# pll-filters.net
KiCad netlist of a schematic drawn in Altium Designer
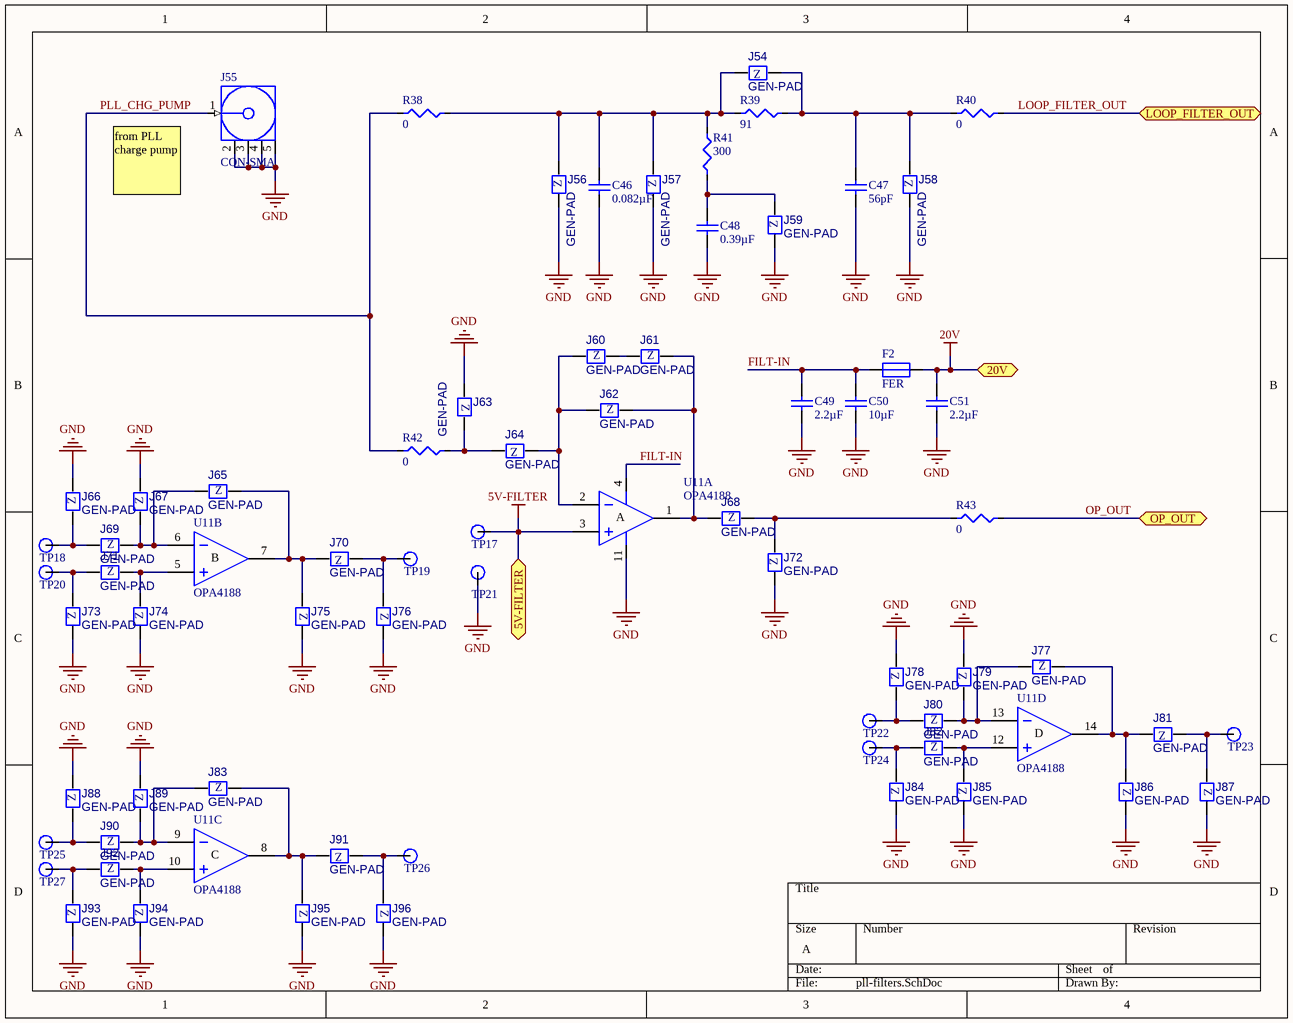
[diagram p0: pll-filters.SchDoc]

(export (version "E")
  (design (tool "Eeschema 10.0.6"))
  (components
    (comp (ref "C46")
      (value "0.082µF")
      (footprint "C0603-0.8MM")
      (description "Capacitor")
      (fields (field (name "EE PART NUMBER") "EE-CAP-00005") (field (name "VOLTAGE") "25V"))
      (libsource (lib "EE") (part "CAP"))
    )
    (comp (ref "C47")
      (value "56pF")
      (footprint "0402-0.55mm")
      (description "Capacitor")
      (fields (field (name "EE PART NUMBER") "EE-CAP-00007") (field (name "VOLTAGE") "50V"))
      (libsource (lib "EE") (part "CAP"))
    )
    (comp (ref "C48")
      (value "0.39µF")
      (footprint "0805-1.35MM")
      (description "Capacitor")
      (fields (field (name "EE PART NUMBER") "EE-CAP-00006") (field (name "VOLTAGE") "25V"))
      (libsource (lib "EE") (part "CAP"))
    )
    (comp (ref "C49")
      (value "2.2µF")
      (footprint "0402-0.55mm")
      (description "Capacitor")
      (fields (field (name "EE PART NUMBER") "EE-CAP-00003") (field (name "VOLTAGE") "35V"))
      (libsource (lib "EE") (part "CAP"))
    )
    (comp (ref "C50")
      (value "10µF")
      (footprint "C0805-1.25MM")
      (description "Capacitor")
      (fields (field (name "EE PART NUMBER") "EE-CAP-00002") (field (name "VOLTAGE") "35V"))
      (libsource (lib "EE") (part "CAP"))
    )
    (comp (ref "C51")
      (value "2.2µF")
      (footprint "0402-0.55mm")
      (description "Capacitor")
      (fields (field (name "EE PART NUMBER") "EE-CAP-00003") (field (name "VOLTAGE") "35V"))
      (libsource (lib "EE") (part "CAP"))
    )
    (comp (ref "F2")
      (value "FER")
      (footprint "0603-0.8mm")
      (fields
        (field (name "EE PART NUMBER") "EE-FER-00001")
        (field (name "MANUFACTURER") "Laird-Signal")
        (field (name "MANUFACTURER PART NUMBER") "HZ0603A222R-10")
      )
      (libsource (lib "EE") (part "FER"))
    )
    (comp (ref "J54")
      (value "GEN-PAD")
      (footprint "0402-DNP")
      (description "Generic Component")
      (fields (field (name "EE PART NUMBER") "EE-GEN-00002"))
      (libsource (lib "EE") (part "GEN-PAD"))
    )
    (comp (ref "J55")
      (value "CON-SMA")
      (footprint "CON-COAX")
      (fields
        (field (name "EE PART NUMBER") "EE-CON-00001")
        (field (name "MANUFACTURER") "East Coast Microwave")
        (field (name "MANUFACTURER PART NUMBER") "PSF-S01-008")
      )
      (libsource (lib "EE") (part "CON-SMA"))
    )
    (comp (ref "J56")
      (value "GEN-PAD")
      (footprint "0805-DNP")
      (description "Generic Component")
      (fields (field (name "EE PART NUMBER") "EE-GEN-00001"))
      (libsource (lib "EE") (part "GEN-PAD"))
    )
    (comp (ref "J57")
      (value "GEN-PAD")
      (footprint "0402-DNP")
      (description "Generic Component")
      (fields (field (name "EE PART NUMBER") "EE-GEN-00002"))
      (libsource (lib "EE") (part "GEN-PAD"))
    )
    (comp (ref "J58")
      (value "GEN-PAD")
      (footprint "0805-DNP")
      (description "Generic Component")
      (fields (field (name "EE PART NUMBER") "EE-GEN-00001"))
      (libsource (lib "EE") (part "GEN-PAD"))
    )
    (comp (ref "J59")
      (value "GEN-PAD")
      (footprint "0402-DNP")
      (description "Generic Component")
      (fields (field (name "EE PART NUMBER") "EE-GEN-00002"))
      (libsource (lib "EE") (part "GEN-PAD"))
    )
    (comp (ref "J60")
      (value "GEN-PAD")
      (footprint "0805-DNP")
      (description "Generic Component")
      (fields (field (name "EE PART NUMBER") "EE-GEN-00001"))
      (libsource (lib "EE") (part "GEN-PAD"))
    )
    (comp (ref "J61")
      (value "GEN-PAD")
      (footprint "0805-DNP")
      (description "Generic Component")
      (fields (field (name "EE PART NUMBER") "EE-GEN-00001"))
      (libsource (lib "EE") (part "GEN-PAD"))
    )
    (comp (ref "J62")
      (value "GEN-PAD")
      (footprint "0805-DNP")
      (description "Generic Component")
      (fields (field (name "EE PART NUMBER") "EE-GEN-00001"))
      (libsource (lib "EE") (part "GEN-PAD"))
    )
    (comp (ref "J63")
      (value "GEN-PAD")
      (footprint "0805-DNP")
      (description "Generic Component")
      (fields (field (name "EE PART NUMBER") "EE-GEN-00001"))
      (libsource (lib "EE") (part "GEN-PAD"))
    )
    (comp (ref "J64")
      (value "GEN-PAD")
      (footprint "0805-DNP")
      (description "Generic Component")
      (fields (field (name "EE PART NUMBER") "EE-GEN-00001"))
      (libsource (lib "EE") (part "GEN-PAD"))
    )
    (comp (ref "J65")
      (value "GEN-PAD")
      (footprint "0805-DNP")
      (description "Generic Component")
      (fields (field (name "EE PART NUMBER") "EE-GEN-00001"))
      (libsource (lib "EE") (part "GEN-PAD"))
    )
    (comp (ref "J66")
      (value "GEN-PAD")
      (footprint "0805-DNP")
      (description "Generic Component")
      (fields (field (name "EE PART NUMBER") "EE-GEN-00001"))
      (libsource (lib "EE") (part "GEN-PAD"))
    )
    (comp (ref "J67")
      (value "GEN-PAD")
      (footprint "0805-DNP")
      (description "Generic Component")
      (fields (field (name "EE PART NUMBER") "EE-GEN-00001"))
      (libsource (lib "EE") (part "GEN-PAD"))
    )
    (comp (ref "J68")
      (value "GEN-PAD")
      (footprint "0805-DNP")
      (description "Generic Component")
      (fields (field (name "EE PART NUMBER") "EE-GEN-00001"))
      (libsource (lib "EE") (part "GEN-PAD"))
    )
    (comp (ref "J69")
      (value "GEN-PAD")
      (footprint "0805-DNP")
      (description "Generic Component")
      (fields (field (name "EE PART NUMBER") "EE-GEN-00001"))
      (libsource (lib "EE") (part "GEN-PAD"))
    )
    (comp (ref "J70")
      (value "GEN-PAD")
      (footprint "0805-DNP")
      (description "Generic Component")
      (fields (field (name "EE PART NUMBER") "EE-GEN-00001"))
      (libsource (lib "EE") (part "GEN-PAD"))
    )
    (comp (ref "J71")
      (value "GEN-PAD")
      (footprint "0805-DNP")
      (description "Generic Component")
      (fields (field (name "EE PART NUMBER") "EE-GEN-00001"))
      (libsource (lib "EE") (part "GEN-PAD"))
    )
    (comp (ref "J72")
      (value "GEN-PAD")
      (footprint "0805-DNP")
      (description "Generic Component")
      (fields (field (name "EE PART NUMBER") "EE-GEN-00001"))
      (libsource (lib "EE") (part "GEN-PAD"))
    )
    (comp (ref "J73")
      (value "GEN-PAD")
      (footprint "0805-DNP")
      (description "Generic Component")
      (fields (field (name "EE PART NUMBER") "EE-GEN-00001"))
      (libsource (lib "EE") (part "GEN-PAD"))
    )
    (comp (ref "J74")
      (value "GEN-PAD")
      (footprint "0805-DNP")
      (description "Generic Component")
      (fields (field (name "EE PART NUMBER") "EE-GEN-00001"))
      (libsource (lib "EE") (part "GEN-PAD"))
    )
    (comp (ref "J75")
      (value "GEN-PAD")
      (footprint "0805-DNP")
      (description "Generic Component")
      (fields (field (name "EE PART NUMBER") "EE-GEN-00001"))
      (libsource (lib "EE") (part "GEN-PAD"))
    )
    (comp (ref "J76")
      (value "GEN-PAD")
      (footprint "0805-DNP")
      (description "Generic Component")
      (fields (field (name "EE PART NUMBER") "EE-GEN-00001"))
      (libsource (lib "EE") (part "GEN-PAD"))
    )
    (comp (ref "J77")
      (value "GEN-PAD")
      (footprint "0805-DNP")
      (description "Generic Component")
      (fields (field (name "EE PART NUMBER") "EE-GEN-00001"))
      (libsource (lib "EE") (part "GEN-PAD"))
    )
    (comp (ref "J78")
      (value "GEN-PAD")
      (footprint "0805-DNP")
      (description "Generic Component")
      (fields (field (name "EE PART NUMBER") "EE-GEN-00001"))
      (libsource (lib "EE") (part "GEN-PAD"))
    )
    (comp (ref "J79")
      (value "GEN-PAD")
      (footprint "0805-DNP")
      (description "Generic Component")
      (fields (field (name "EE PART NUMBER") "EE-GEN-00001"))
      (libsource (lib "EE") (part "GEN-PAD"))
    )
    (comp (ref "J80")
      (value "GEN-PAD")
      (footprint "0805-DNP")
      (description "Generic Component")
      (fields (field (name "EE PART NUMBER") "EE-GEN-00001"))
      (libsource (lib "EE") (part "GEN-PAD"))
    )
    (comp (ref "J81")
      (value "GEN-PAD")
      (footprint "0805-DNP")
      (description "Generic Component")
      (fields (field (name "EE PART NUMBER") "EE-GEN-00001"))
      (libsource (lib "EE") (part "GEN-PAD"))
    )
    (comp (ref "J82")
      (value "GEN-PAD")
      (footprint "0805-DNP")
      (description "Generic Component")
      (fields (field (name "EE PART NUMBER") "EE-GEN-00001"))
      (libsource (lib "EE") (part "GEN-PAD"))
    )
    (comp (ref "J83")
      (value "GEN-PAD")
      (footprint "0805-DNP")
      (description "Generic Component")
      (fields (field (name "EE PART NUMBER") "EE-GEN-00001"))
      (libsource (lib "EE") (part "GEN-PAD"))
    )
    (comp (ref "J84")
      (value "GEN-PAD")
      (footprint "0805-DNP")
      (description "Generic Component")
      (fields (field (name "EE PART NUMBER") "EE-GEN-00001"))
      (libsource (lib "EE") (part "GEN-PAD"))
    )
    (comp (ref "J85")
      (value "GEN-PAD")
      (footprint "0805-DNP")
      (description "Generic Component")
      (fields (field (name "EE PART NUMBER") "EE-GEN-00001"))
      (libsource (lib "EE") (part "GEN-PAD"))
    )
    (comp (ref "J86")
      (value "GEN-PAD")
      (footprint "0805-DNP")
      (description "Generic Component")
      (fields (field (name "EE PART NUMBER") "EE-GEN-00001"))
      (libsource (lib "EE") (part "GEN-PAD"))
    )
    (comp (ref "J87")
      (value "GEN-PAD")
      (footprint "0805-DNP")
      (description "Generic Component")
      (fields (field (name "EE PART NUMBER") "EE-GEN-00001"))
      (libsource (lib "EE") (part "GEN-PAD"))
    )
    (comp (ref "J88")
      (value "GEN-PAD")
      (footprint "0805-DNP")
      (description "Generic Component")
      (fields (field (name "EE PART NUMBER") "EE-GEN-00001"))
      (libsource (lib "EE") (part "GEN-PAD"))
    )
    (comp (ref "J89")
      (value "GEN-PAD")
      (footprint "0805-DNP")
      (description "Generic Component")
      (fields (field (name "EE PART NUMBER") "EE-GEN-00001"))
      (libsource (lib "EE") (part "GEN-PAD"))
    )
    (comp (ref "J90")
      (value "GEN-PAD")
      (footprint "0805-DNP")
      (description "Generic Component")
      (fields (field (name "EE PART NUMBER") "EE-GEN-00001"))
      (libsource (lib "EE") (part "GEN-PAD"))
    )
    (comp (ref "J91")
      (value "GEN-PAD")
      (footprint "0805-DNP")
      (description "Generic Component")
      (fields (field (name "EE PART NUMBER") "EE-GEN-00001"))
      (libsource (lib "EE") (part "GEN-PAD"))
    )
    (comp (ref "J92")
      (value "GEN-PAD")
      (footprint "0805-DNP")
      (description "Generic Component")
      (fields (field (name "EE PART NUMBER") "EE-GEN-00001"))
      (libsource (lib "EE") (part "GEN-PAD"))
    )
    (comp (ref "J93")
      (value "GEN-PAD")
      (footprint "0805-DNP")
      (description "Generic Component")
      (fields (field (name "EE PART NUMBER") "EE-GEN-00001"))
      (libsource (lib "EE") (part "GEN-PAD"))
    )
    (comp (ref "J94")
      (value "GEN-PAD")
      (footprint "0805-DNP")
      (description "Generic Component")
      (fields (field (name "EE PART NUMBER") "EE-GEN-00001"))
      (libsource (lib "EE") (part "GEN-PAD"))
    )
    (comp (ref "J95")
      (value "GEN-PAD")
      (footprint "0805-DNP")
      (description "Generic Component")
      (fields (field (name "EE PART NUMBER") "EE-GEN-00001"))
      (libsource (lib "EE") (part "GEN-PAD"))
    )
    (comp (ref "J96")
      (value "GEN-PAD")
      (footprint "0805-DNP")
      (description "Generic Component")
      (fields (field (name "EE PART NUMBER") "EE-GEN-00001"))
      (libsource (lib "EE") (part "GEN-PAD"))
    )
    (comp (ref "R38")
      (value "0")
      (footprint "0805-0.45MM")
      (fields
        (field (name "EM PART NUMBER") "EM-RES-01617")
        (field (name "POWER") "0.33W")
        (field (name "MANUFACTURER") "Vishay")
      )
      (libsource (lib "EM") (part "RES"))
    )
    (comp (ref "R39")
      (value "91")
      (footprint "0805-0.45MM")
      (fields
        (field (name "EM PART NUMBER") "EM-RES-01374")
        (field (name "TOLERANCE") "1%")
        (field (name "POWER") "0.125W")
      )
      (libsource (lib "EM") (part "RES"))
    )
    (comp (ref "R40")
      (value "0")
      (footprint "0805-0.45MM")
      (fields
        (field (name "EM PART NUMBER") "EM-RES-01617")
        (field (name "POWER") "0.33W")
        (field (name "MANUFACTURER") "Vishay")
      )
      (libsource (lib "EM") (part "RES"))
    )
    (comp (ref "R41")
      (value "300")
      (footprint "0805-0.45MM")
      (fields
        (field (name "EM PART NUMBER") "EM-RES-01318")
        (field (name "TOLERANCE") "1%")
        (field (name "POWER") "0.125W")
      )
      (libsource (lib "EM") (part "RES"))
    )
    (comp (ref "R42")
      (value "0")
      (footprint "0805-0.45MM")
      (fields
        (field (name "EM PART NUMBER") "EM-RES-01617")
        (field (name "POWER") "0.33W")
        (field (name "MANUFACTURER") "Vishay")
      )
      (libsource (lib "EM") (part "RES"))
    )
    (comp (ref "R43")
      (value "0")
      (footprint "0805-0.45MM")
      (fields
        (field (name "EM PART NUMBER") "EM-RES-01617")
        (field (name "POWER") "0.33W")
        (field (name "MANUFACTURER") "Vishay")
      )
      (libsource (lib "EM") (part "RES"))
    )
    (comp (ref "TP17")
      (value "TP-LOOP")
      (footprint "TP-LOOP")
      (fields (field (name "EM PART NUMBER") "EM-TP-00006"))
      (libsource (lib "EM") (part "TP-LOOP"))
    )
    (comp (ref "TP18")
      (value "TP-LOOP")
      (footprint "TP-LOOP")
      (fields (field (name "EM PART NUMBER") "EM-TP-00006"))
      (libsource (lib "EM") (part "TP-LOOP"))
    )
    (comp (ref "TP19")
      (value "TP-LOOP")
      (footprint "TP-LOOP")
      (fields (field (name "EM PART NUMBER") "EM-TP-00006"))
      (libsource (lib "EM") (part "TP-LOOP"))
    )
    (comp (ref "TP20")
      (value "TP-LOOP")
      (footprint "TP-LOOP")
      (fields (field (name "EM PART NUMBER") "EM-TP-00006"))
      (libsource (lib "EM") (part "TP-LOOP"))
    )
    (comp (ref "TP21")
      (value "TP-LOOP")
      (footprint "TP-LOOP")
      (fields (field (name "EM PART NUMBER") "EM-TP-00006"))
      (libsource (lib "EM") (part "TP-LOOP"))
    )
    (comp (ref "TP22")
      (value "TP-LOOP")
      (footprint "TP-LOOP")
      (fields (field (name "EM PART NUMBER") "EM-TP-00006"))
      (libsource (lib "EM") (part "TP-LOOP"))
    )
    (comp (ref "TP23")
      (value "TP-LOOP")
      (footprint "TP-LOOP")
      (fields (field (name "EM PART NUMBER") "EM-TP-00006"))
      (libsource (lib "EM") (part "TP-LOOP"))
    )
    (comp (ref "TP24")
      (value "TP-LOOP")
      (footprint "TP-LOOP")
      (fields (field (name "EM PART NUMBER") "EM-TP-00006"))
      (libsource (lib "EM") (part "TP-LOOP"))
    )
    (comp (ref "TP25")
      (value "TP-LOOP")
      (footprint "TP-LOOP")
      (fields (field (name "EM PART NUMBER") "EM-TP-00006"))
      (libsource (lib "EM") (part "TP-LOOP"))
    )
    (comp (ref "TP26")
      (value "TP-LOOP")
      (footprint "TP-LOOP")
      (fields (field (name "EM PART NUMBER") "EM-TP-00006"))
      (libsource (lib "EM") (part "TP-LOOP"))
    )
    (comp (ref "TP27")
      (value "TP-LOOP")
      (footprint "TP-LOOP")
      (fields (field (name "EM PART NUMBER") "EM-TP-00006"))
      (libsource (lib "EM") (part "TP-LOOP"))
    )
    (comp (ref "U11")
      (value "OPA4188")
      (footprint "TSSOP14")
      (description "Quad Op-Aamp")
      (fields
        (field (name "EE PART NUMBER") "EE-OPAMP-00004")
        (field (name "VOLTAGE") "4 V ~ 36 V, ±2 V ~ 18 V")
      )
      (libsource (lib "EE") (part "OPA4188"))
    )
  )
  (nets
    (net (code "1") (name "/FILT-IN") (class "Default")
      (node (ref "C49") (pin "2") (pinfunction "2_2") (pintype "passive"))
      (node (ref "C50") (pin "2") (pinfunction "2_2") (pintype "passive"))
      (node (ref "F2") (pin "2") (pinfunction "2_2") (pintype "passive"))
      (node (ref "U11") (pin "4") (pinfunction "V+_4") (pintype "power_in"))
    )
    (net (code "2") (name "/LOOP_FILTER_OUT") (class "Default")
      (node (ref "R40") (pin "2") (pinfunction "2_2") (pintype "passive"))
    )
    (net (code "3") (name "/OP_OUT") (class "Default")
      (node (ref "R43") (pin "2") (pinfunction "2_2") (pintype "passive"))
    )
    (net (code "4") (name "/PLL_CHG_PUMP") (class "Default")
      (node (ref "J55") (pin "1") (pinfunction "Signal_1") (pintype "input"))
      (node (ref "R38") (pin "1") (pinfunction "1_1") (pintype "passive"))
      (node (ref "R42") (pin "1") (pinfunction "1_1") (pintype "passive"))
    )
    (net (code "5") (name "5V-FILTER") (class "Default")
      (node (ref "TP17") (pin "0") (pinfunction "0_0") (pintype "passive"))
      (node (ref "U11") (pin "3") (pinfunction "IN+_3") (pintype "passive"))
    )
    (net (code "6") (name "20V") (class "Default")
      (node (ref "C51") (pin "2") (pinfunction "2_2") (pintype "passive"))
      (node (ref "F2") (pin "1") (pinfunction "1_1") (pintype "passive"))
    )
    (net (code "7") (name "GND") (class "Default")
      (node (ref "C46") (pin "1") (pinfunction "1_1") (pintype "passive"))
      (node (ref "C47") (pin "1") (pinfunction "1_1") (pintype "passive"))
      (node (ref "C48") (pin "1") (pinfunction "1_1") (pintype "passive"))
      (node (ref "C49") (pin "1") (pinfunction "1_1") (pintype "passive"))
      (node (ref "C50") (pin "1") (pinfunction "1_1") (pintype "passive"))
      (node (ref "C51") (pin "1") (pinfunction "1_1") (pintype "passive"))
      (node (ref "J55") (pin "2") (pinfunction "GND_2") (pintype "power_in"))
      (node (ref "J55") (pin "3") (pinfunction "GND_3") (pintype "power_in"))
      (node (ref "J55") (pin "4") (pinfunction "GND_4") (pintype "power_in"))
      (node (ref "J55") (pin "5") (pinfunction "GND_5") (pintype "power_in"))
      (node (ref "J56") (pin "2") (pinfunction "2_2") (pintype "passive"))
      (node (ref "J57") (pin "2") (pinfunction "2_2") (pintype "passive"))
      (node (ref "J58") (pin "2") (pinfunction "2_2") (pintype "passive"))
      (node (ref "J59") (pin "2") (pinfunction "2_2") (pintype "passive"))
      (node (ref "J63") (pin "2") (pinfunction "2_2") (pintype "passive"))
      (node (ref "J66") (pin "1") (pinfunction "1_1") (pintype "passive"))
      (node (ref "J67") (pin "1") (pinfunction "1_1") (pintype "passive"))
      (node (ref "J72") (pin "2") (pinfunction "2_2") (pintype "passive"))
      (node (ref "J73") (pin "2") (pinfunction "2_2") (pintype "passive"))
      (node (ref "J74") (pin "2") (pinfunction "2_2") (pintype "passive"))
      (node (ref "J75") (pin "1") (pinfunction "1_1") (pintype "passive"))
      (node (ref "J76") (pin "1") (pinfunction "1_1") (pintype "passive"))
      (node (ref "J78") (pin "1") (pinfunction "1_1") (pintype "passive"))
      (node (ref "J79") (pin "1") (pinfunction "1_1") (pintype "passive"))
      (node (ref "J84") (pin "2") (pinfunction "2_2") (pintype "passive"))
      (node (ref "J85") (pin "2") (pinfunction "2_2") (pintype "passive"))
      (node (ref "J86") (pin "1") (pinfunction "1_1") (pintype "passive"))
      (node (ref "J87") (pin "1") (pinfunction "1_1") (pintype "passive"))
      (node (ref "J88") (pin "1") (pinfunction "1_1") (pintype "passive"))
      (node (ref "J89") (pin "1") (pinfunction "1_1") (pintype "passive"))
      (node (ref "J93") (pin "2") (pinfunction "2_2") (pintype "passive"))
      (node (ref "J94") (pin "2") (pinfunction "2_2") (pintype "passive"))
      (node (ref "J95") (pin "1") (pinfunction "1_1") (pintype "passive"))
      (node (ref "J96") (pin "1") (pinfunction "1_1") (pintype "passive"))
      (node (ref "TP21") (pin "0") (pinfunction "0_0") (pintype "passive"))
      (node (ref "U11") (pin "11") (pinfunction "V-_11") (pintype "power_in"))
    )
    (net (code "8") (name "Net-(C46-Pad2)") (class "Default")
      (node (ref "C46") (pin "2") (pinfunction "2_2") (pintype "passive"))
      (node (ref "J54") (pin "1") (pinfunction "1_1") (pintype "passive"))
      (node (ref "J56") (pin "1") (pinfunction "1_1") (pintype "passive"))
      (node (ref "J57") (pin "1") (pinfunction "1_1") (pintype "passive"))
      (node (ref "R38") (pin "2") (pinfunction "2_2") (pintype "passive"))
      (node (ref "R39") (pin "1") (pinfunction "1_1") (pintype "passive"))
      (node (ref "R41") (pin "2") (pinfunction "2_2") (pintype "passive"))
    )
    (net (code "9") (name "Net-(C47-Pad2)") (class "Default")
      (node (ref "C47") (pin "2") (pinfunction "2_2") (pintype "passive"))
      (node (ref "J54") (pin "2") (pinfunction "2_2") (pintype "passive"))
      (node (ref "J58") (pin "1") (pinfunction "1_1") (pintype "passive"))
      (node (ref "R39") (pin "2") (pinfunction "2_2") (pintype "passive"))
      (node (ref "R40") (pin "1") (pinfunction "1_1") (pintype "passive"))
    )
    (net (code "10") (name "Net-(C48-Pad2)") (class "Default")
      (node (ref "C48") (pin "2") (pinfunction "2_2") (pintype "passive"))
      (node (ref "J59") (pin "1") (pinfunction "1_1") (pintype "passive"))
      (node (ref "R41") (pin "1") (pinfunction "1_1") (pintype "passive"))
    )
    (net (code "11") (name "Net-(J60-Pad1)") (class "Default")
      (node (ref "J60") (pin "1") (pinfunction "1_1") (pintype "passive"))
      (node (ref "J61") (pin "2") (pinfunction "2_2") (pintype "passive"))
    )
    (net (code "12") (name "Net-(J63-Pad1)") (class "Default")
      (node (ref "J63") (pin "1") (pinfunction "1_1") (pintype "passive"))
      (node (ref "J64") (pin "1") (pinfunction "1_1") (pintype "passive"))
      (node (ref "R42") (pin "2") (pinfunction "2_2") (pintype "passive"))
    )
    (net (code "13") (name "Net-(J66-Pad2)") (class "Default")
      (node (ref "J66") (pin "2") (pinfunction "2_2") (pintype "passive"))
      (node (ref "J69") (pin "2") (pinfunction "2_2") (pintype "passive"))
      (node (ref "TP18") (pin "0") (pinfunction "0_0") (pintype "passive"))
    )
    (net (code "14") (name "Net-(J68-Pad1)") (class "Default")
      (node (ref "J68") (pin "1") (pinfunction "1_1") (pintype "passive"))
      (node (ref "J72") (pin "1") (pinfunction "1_1") (pintype "passive"))
      (node (ref "R43") (pin "1") (pinfunction "1_1") (pintype "passive"))
    )
    (net (code "15") (name "Net-(J70-Pad2)") (class "Default")
      (node (ref "J70") (pin "2") (pinfunction "2_2") (pintype "passive"))
      (node (ref "J76") (pin "2") (pinfunction "2_2") (pintype "passive"))
      (node (ref "TP19") (pin "0") (pinfunction "0_0") (pintype "passive"))
    )
    (net (code "16") (name "Net-(J71-Pad2)") (class "Default")
      (node (ref "J71") (pin "2") (pinfunction "2_2") (pintype "passive"))
      (node (ref "J73") (pin "1") (pinfunction "1_1") (pintype "passive"))
      (node (ref "TP20") (pin "0") (pinfunction "0_0") (pintype "passive"))
    )
    (net (code "17") (name "Net-(J78-Pad2)") (class "Default")
      (node (ref "J78") (pin "2") (pinfunction "2_2") (pintype "passive"))
      (node (ref "J80") (pin "2") (pinfunction "2_2") (pintype "passive"))
      (node (ref "TP22") (pin "0") (pinfunction "0_0") (pintype "passive"))
    )
    (net (code "18") (name "Net-(J81-Pad2)") (class "Default")
      (node (ref "J81") (pin "2") (pinfunction "2_2") (pintype "passive"))
      (node (ref "J87") (pin "2") (pinfunction "2_2") (pintype "passive"))
      (node (ref "TP23") (pin "0") (pinfunction "0_0") (pintype "passive"))
    )
    (net (code "19") (name "Net-(J82-Pad2)") (class "Default")
      (node (ref "J82") (pin "2") (pinfunction "2_2") (pintype "passive"))
      (node (ref "J84") (pin "1") (pinfunction "1_1") (pintype "passive"))
      (node (ref "TP24") (pin "0") (pinfunction "0_0") (pintype "passive"))
    )
    (net (code "20") (name "Net-(J88-Pad2)") (class "Default")
      (node (ref "J88") (pin "2") (pinfunction "2_2") (pintype "passive"))
      (node (ref "J90") (pin "2") (pinfunction "2_2") (pintype "passive"))
      (node (ref "TP25") (pin "0") (pinfunction "0_0") (pintype "passive"))
    )
    (net (code "21") (name "Net-(J91-Pad2)") (class "Default")
      (node (ref "J91") (pin "2") (pinfunction "2_2") (pintype "passive"))
      (node (ref "J96") (pin "2") (pinfunction "2_2") (pintype "passive"))
      (node (ref "TP26") (pin "0") (pinfunction "0_0") (pintype "passive"))
    )
    (net (code "22") (name "Net-(J92-Pad2)") (class "Default")
      (node (ref "J92") (pin "2") (pinfunction "2_2") (pintype "passive"))
      (node (ref "J93") (pin "1") (pinfunction "1_1") (pintype "passive"))
      (node (ref "TP27") (pin "0") (pinfunction "0_0") (pintype "passive"))
    )
    (net (code "23") (name "Net-(U11A-IN-)") (class "Default")
      (node (ref "J60") (pin "2") (pinfunction "2_2") (pintype "passive"))
      (node (ref "J62") (pin "2") (pinfunction "2_2") (pintype "passive"))
      (node (ref "J64") (pin "2") (pinfunction "2_2") (pintype "passive"))
      (node (ref "U11") (pin "2") (pinfunction "IN-_2") (pintype "passive"))
    )
    (net (code "24") (name "Net-(U11A-OUT)") (class "Default")
      (node (ref "J61") (pin "1") (pinfunction "1_1") (pintype "passive"))
      (node (ref "J62") (pin "1") (pinfunction "1_1") (pintype "passive"))
      (node (ref "J68") (pin "2") (pinfunction "2_2") (pintype "passive"))
      (node (ref "U11") (pin "1") (pinfunction "OUT_1") (pintype "passive"))
    )
    (net (code "25") (name "Net-(U11B-IN+)") (class "Default")
      (node (ref "J71") (pin "1") (pinfunction "1_1") (pintype "passive"))
      (node (ref "J74") (pin "1") (pinfunction "1_1") (pintype "passive"))
      (node (ref "U11") (pin "5") (pinfunction "IN+_5") (pintype "passive"))
    )
    (net (code "26") (name "Net-(U11B-IN-)") (class "Default")
      (node (ref "J65") (pin "2") (pinfunction "2_2") (pintype "passive"))
      (node (ref "J67") (pin "2") (pinfunction "2_2") (pintype "passive"))
      (node (ref "J69") (pin "1") (pinfunction "1_1") (pintype "passive"))
      (node (ref "U11") (pin "6") (pinfunction "IN-_6") (pintype "passive"))
    )
    (net (code "27") (name "Net-(U11B-OUT)") (class "Default")
      (node (ref "J65") (pin "1") (pinfunction "1_1") (pintype "passive"))
      (node (ref "J70") (pin "1") (pinfunction "1_1") (pintype "passive"))
      (node (ref "J75") (pin "2") (pinfunction "2_2") (pintype "passive"))
      (node (ref "U11") (pin "7") (pinfunction "OUT_7") (pintype "passive"))
    )
    (net (code "28") (name "Net-(U11C-IN+)") (class "Default")
      (node (ref "J92") (pin "1") (pinfunction "1_1") (pintype "passive"))
      (node (ref "J94") (pin "1") (pinfunction "1_1") (pintype "passive"))
      (node (ref "U11") (pin "10") (pinfunction "IN+_10") (pintype "passive"))
    )
    (net (code "29") (name "Net-(U11C-IN-)") (class "Default")
      (node (ref "J83") (pin "2") (pinfunction "2_2") (pintype "passive"))
      (node (ref "J89") (pin "2") (pinfunction "2_2") (pintype "passive"))
      (node (ref "J90") (pin "1") (pinfunction "1_1") (pintype "passive"))
      (node (ref "U11") (pin "9") (pinfunction "IN-_9") (pintype "passive"))
    )
    (net (code "30") (name "Net-(U11C-OUT)") (class "Default")
      (node (ref "J83") (pin "1") (pinfunction "1_1") (pintype "passive"))
      (node (ref "J91") (pin "1") (pinfunction "1_1") (pintype "passive"))
      (node (ref "J95") (pin "2") (pinfunction "2_2") (pintype "passive"))
      (node (ref "U11") (pin "8") (pinfunction "OUT_8") (pintype "passive"))
    )
    (net (code "31") (name "Net-(U11D-IN+)") (class "Default")
      (node (ref "J82") (pin "1") (pinfunction "1_1") (pintype "passive"))
      (node (ref "J85") (pin "1") (pinfunction "1_1") (pintype "passive"))
      (node (ref "U11") (pin "12") (pinfunction "IN+_12") (pintype "passive"))
    )
    (net (code "32") (name "Net-(U11D-IN-)") (class "Default")
      (node (ref "J77") (pin "2") (pinfunction "2_2") (pintype "passive"))
      (node (ref "J79") (pin "2") (pinfunction "2_2") (pintype "passive"))
      (node (ref "J80") (pin "1") (pinfunction "1_1") (pintype "passive"))
      (node (ref "U11") (pin "13") (pinfunction "IN-_13") (pintype "passive"))
    )
    (net (code "33") (name "Net-(U11D-OUT)") (class "Default")
      (node (ref "J77") (pin "1") (pinfunction "1_1") (pintype "passive"))
      (node (ref "J81") (pin "1") (pinfunction "1_1") (pintype "passive"))
      (node (ref "J86") (pin "2") (pinfunction "2_2") (pintype "passive"))
      (node (ref "U11") (pin "14") (pinfunction "OUT_14") (pintype "passive"))
    )
  )
)
